# RF.net
KiCad netlist of a schematic drawn in Altium Designer
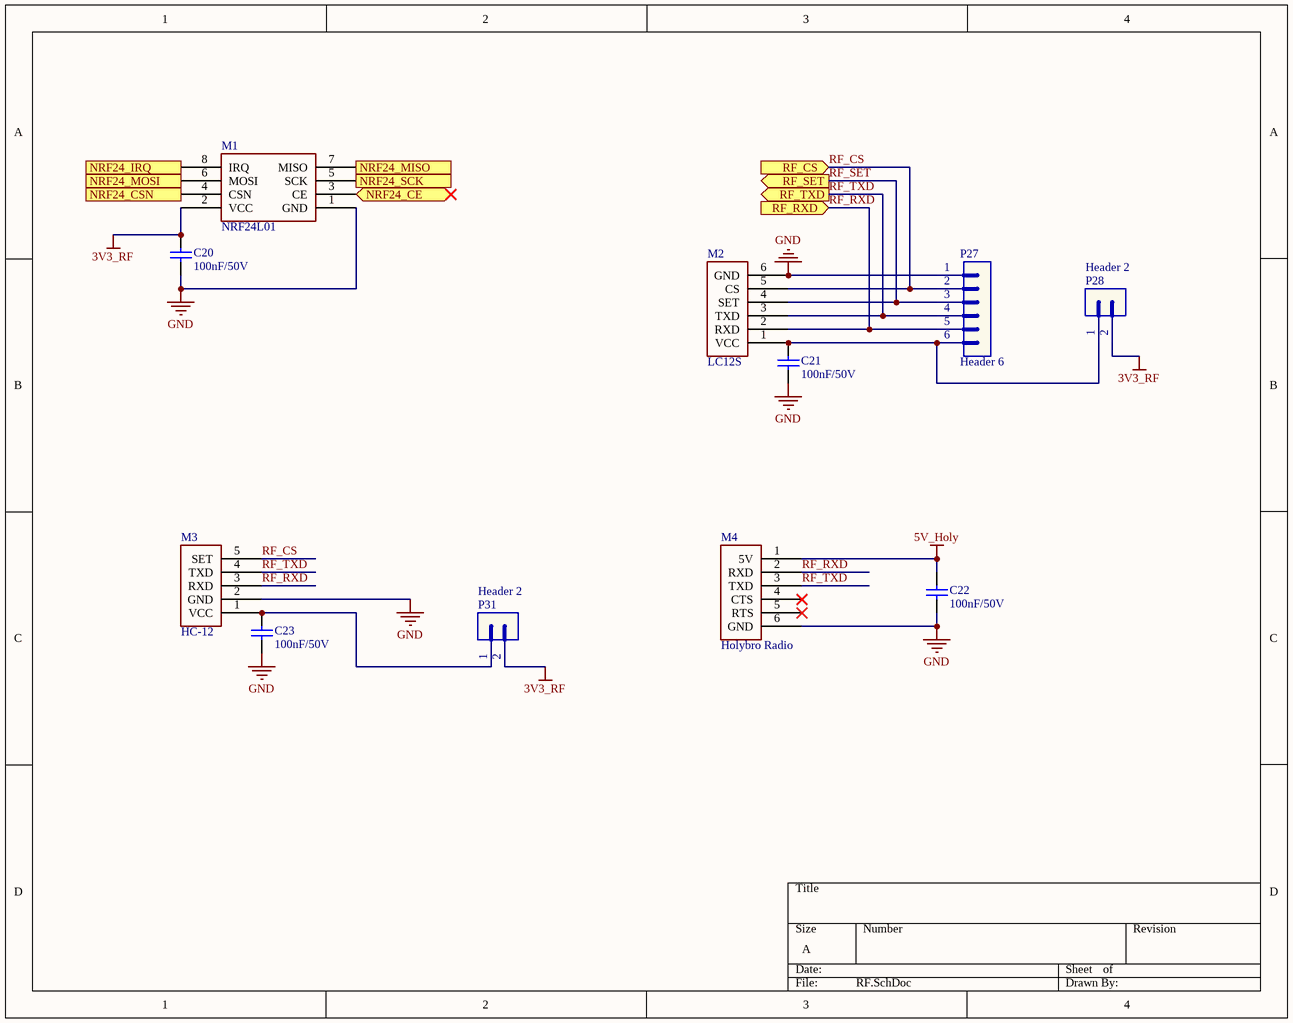
[diagram p0: RF.SchDoc]

(export (version "E")
  (design (tool "Eeschema 10.0.6"))
  (components
    (comp (ref "C20")
      (value "100nF/50V")
      (footprint "CAP-SM-0805")
      (description "CAP CER 0.1UF 50V Y5V 0805")
      (fields
        (field (name "MANUFACTURER") "Samsung Electro-Mechanics")
        (field (name "MANUFACTURER PART NUMBER") "CL21F104ZBCNNNC")
      )
      (libsource (lib "Capacitor") (part "Cap-100nF-50V-0805"))
    )
    (comp (ref "C21")
      (value "100nF/50V")
      (footprint "CAP-SM-0805")
      (description "CAP CER 0.1UF 50V Y5V 0805")
      (fields
        (field (name "MANUFACTURER") "Samsung Electro-Mechanics")
        (field (name "MANUFACTURER PART NUMBER") "CL21F104ZBCNNNC")
      )
      (libsource (lib "Capacitor") (part "Cap-100nF-50V-0805"))
    )
    (comp (ref "C22")
      (value "100nF/50V")
      (footprint "CAP-SM-0805")
      (description "CAP CER 0.1UF 50V Y5V 0805")
      (fields
        (field (name "MANUFACTURER") "Samsung Electro-Mechanics")
        (field (name "MANUFACTURER PART NUMBER") "CL21F104ZBCNNNC")
      )
      (libsource (lib "Capacitor") (part "Cap-100nF-50V-0805"))
    )
    (comp (ref "C23")
      (value "100nF/50V")
      (footprint "CAP-SM-0805")
      (description "CAP CER 0.1UF 50V Y5V 0805")
      (fields
        (field (name "MANUFACTURER") "Samsung Electro-Mechanics")
        (field (name "MANUFACTURER PART NUMBER") "CL21F104ZBCNNNC")
      )
      (libsource (lib "Capacitor") (part "Cap-100nF-50V-0805"))
    )
    (comp (ref "M1")
      (value "NRF24L01")
      (footprint "NRF24L01")
      (fields (field (name "LOCAL SUPPLIER PART NUMBER") "HS000888"))
      (libsource (lib "PIF_robot") (part "NRF24L01"))
    )
    (comp (ref "M2")
      (value "LC12S")
      (footprint "LC12S")
      (fields (field (name "LOCAL SUPPLIER PART NUMBER") "HS00095"))
      (libsource (lib "PIF_robot") (part "LC12S"))
    )
    (comp (ref "M3")
      (value "HC-12")
      (footprint "HC-12")
      (fields (field (name "LOCAL SUPPLIER PART NUMBER") "HS000897"))
      (libsource (lib "PIF_robot") (part "HC-12"))
    )
    (comp (ref "M4")
      (value "Holybro Radio")
      (footprint "Holybro-Radio")
      (libsource (lib "PIF_robot") (part "Holybro Radio"))
    )
    (comp (ref "P27")
      (value "Header 6")
      (footprint "JP6")
      (description "Header, 6-Pin")
      (fields (field (name "PUBLISHER") "Altium Limited"))
      (libsource (lib "Header-Connector") (part "Header 6"))
    )
    (comp (ref "P28")
      (value "Header 2")
      (footprint "JP2")
      (description "Header, 2-Pin")
      (fields (field (name "PUBLISHER") "Altium Limited"))
      (libsource (lib "Header-Connector") (part "Header 2"))
    )
    (comp (ref "P31")
      (value "Header 2")
      (footprint "JP2")
      (description "Header, 2-Pin")
      (fields (field (name "PUBLISHER") "Altium Limited"))
      (libsource (lib "Header-Connector") (part "Header 2"))
    )
  )
  (nets
    (net (code "1") (name "/NRF24_CE") (class "Default")
      (node (ref "M1") (pin "3") (pinfunction "CE_3") (pintype "passive"))
    )
    (net (code "2") (name "/NRF24_CSN") (class "Default")
      (node (ref "M1") (pin "4") (pinfunction "CSN_4") (pintype "passive"))
    )
    (net (code "3") (name "/NRF24_IRQ") (class "Default")
      (node (ref "M1") (pin "8") (pinfunction "IRQ_8") (pintype "passive"))
    )
    (net (code "4") (name "/NRF24_MISO") (class "Default")
      (node (ref "M1") (pin "7") (pinfunction "MISO_7") (pintype "passive"))
    )
    (net (code "5") (name "/NRF24_MOSI") (class "Default")
      (node (ref "M1") (pin "6") (pinfunction "MOSI_6") (pintype "passive"))
    )
    (net (code "6") (name "/NRF24_SCK") (class "Default")
      (node (ref "M1") (pin "5") (pinfunction "SCK_5") (pintype "passive"))
    )
    (net (code "7") (name "/RF_CS") (class "Default")
      (node (ref "M2") (pin "5") (pinfunction "CS_5") (pintype "passive"))
      (node (ref "M3") (pin "5") (pinfunction "SET_5") (pintype "passive"))
      (node (ref "P27") (pin "2") (pinfunction "2_2") (pintype "passive"))
    )
    (net (code "8") (name "/RF_RXD") (class "Default")
      (node (ref "M2") (pin "2") (pinfunction "RXD_2") (pintype "passive"))
      (node (ref "M3") (pin "3") (pinfunction "RXD_3") (pintype "passive"))
      (node (ref "M4") (pin "2") (pinfunction "RXD_2") (pintype "passive"))
      (node (ref "P27") (pin "5") (pinfunction "5_5") (pintype "passive"))
    )
    (net (code "9") (name "/RF_SET") (class "Default")
      (node (ref "M2") (pin "4") (pinfunction "SET_4") (pintype "passive"))
      (node (ref "P27") (pin "3") (pinfunction "3_3") (pintype "passive"))
    )
    (net (code "10") (name "/RF_TXD") (class "Default")
      (node (ref "M2") (pin "3") (pinfunction "TXD_3") (pintype "passive"))
      (node (ref "M3") (pin "4") (pinfunction "TXD_4") (pintype "passive"))
      (node (ref "M4") (pin "3") (pinfunction "TXD_3") (pintype "passive"))
      (node (ref "P27") (pin "4") (pinfunction "4_4") (pintype "passive"))
    )
    (net (code "11") (name "3V3_RF") (class "Default")
      (node (ref "C20") (pin "2") (pinfunction "2_2") (pintype "passive"))
      (node (ref "M1") (pin "2") (pinfunction "VCC_2") (pintype "passive"))
      (node (ref "P28") (pin "2") (pinfunction "2_2") (pintype "passive"))
      (node (ref "P31") (pin "2") (pinfunction "2_2") (pintype "passive"))
    )
    (net (code "12") (name "5V_Holy") (class "Default")
      (node (ref "C22") (pin "2") (pinfunction "2_2") (pintype "passive"))
      (node (ref "M4") (pin "1") (pinfunction "5V_1") (pintype "passive"))
    )
    (net (code "13") (name "GND") (class "Default")
      (node (ref "C20") (pin "1") (pinfunction "1_1") (pintype "passive"))
      (node (ref "C21") (pin "1") (pinfunction "1_1") (pintype "passive"))
      (node (ref "C22") (pin "1") (pinfunction "1_1") (pintype "passive"))
      (node (ref "C23") (pin "1") (pinfunction "1_1") (pintype "passive"))
      (node (ref "M1") (pin "1") (pinfunction "GND_1") (pintype "passive"))
      (node (ref "M2") (pin "6") (pinfunction "GND_6") (pintype "power_in"))
      (node (ref "M3") (pin "2") (pinfunction "GND_2") (pintype "passive"))
      (node (ref "M4") (pin "6") (pinfunction "GND_6") (pintype "passive"))
      (node (ref "P27") (pin "1") (pinfunction "1_1") (pintype "passive"))
    )
    (net (code "14") (name "Net-(M2-VCC)") (class "Default")
      (node (ref "C21") (pin "2") (pinfunction "2_2") (pintype "passive"))
      (node (ref "M2") (pin "1") (pinfunction "VCC_1") (pintype "power_in"))
      (node (ref "P27") (pin "6") (pinfunction "6_6") (pintype "passive"))
      (node (ref "P28") (pin "1") (pinfunction "1_1") (pintype "passive"))
    )
    (net (code "15") (name "Net-(M3-VCC)") (class "Default")
      (node (ref "C23") (pin "2") (pinfunction "2_2") (pintype "passive"))
      (node (ref "M3") (pin "1") (pinfunction "VCC_1") (pintype "passive"))
      (node (ref "P31") (pin "1") (pinfunction "1_1") (pintype "passive"))
    )
    (net (code "16") (name "unconnected-(M4-CTS-Pad4)") (class "Default")
      (node (ref "M4") (pin "4") (pinfunction "CTS_4") (pintype "passive+no_connect"))
    )
    (net (code "17") (name "unconnected-(M4-RTS-Pad5)") (class "Default")
      (node (ref "M4") (pin "5") (pinfunction "RTS_5") (pintype "passive+no_connect"))
    )
  )
)
